# MCU_oscilliation.net
KiCad netlist of a schematic drawn in Altium Designer
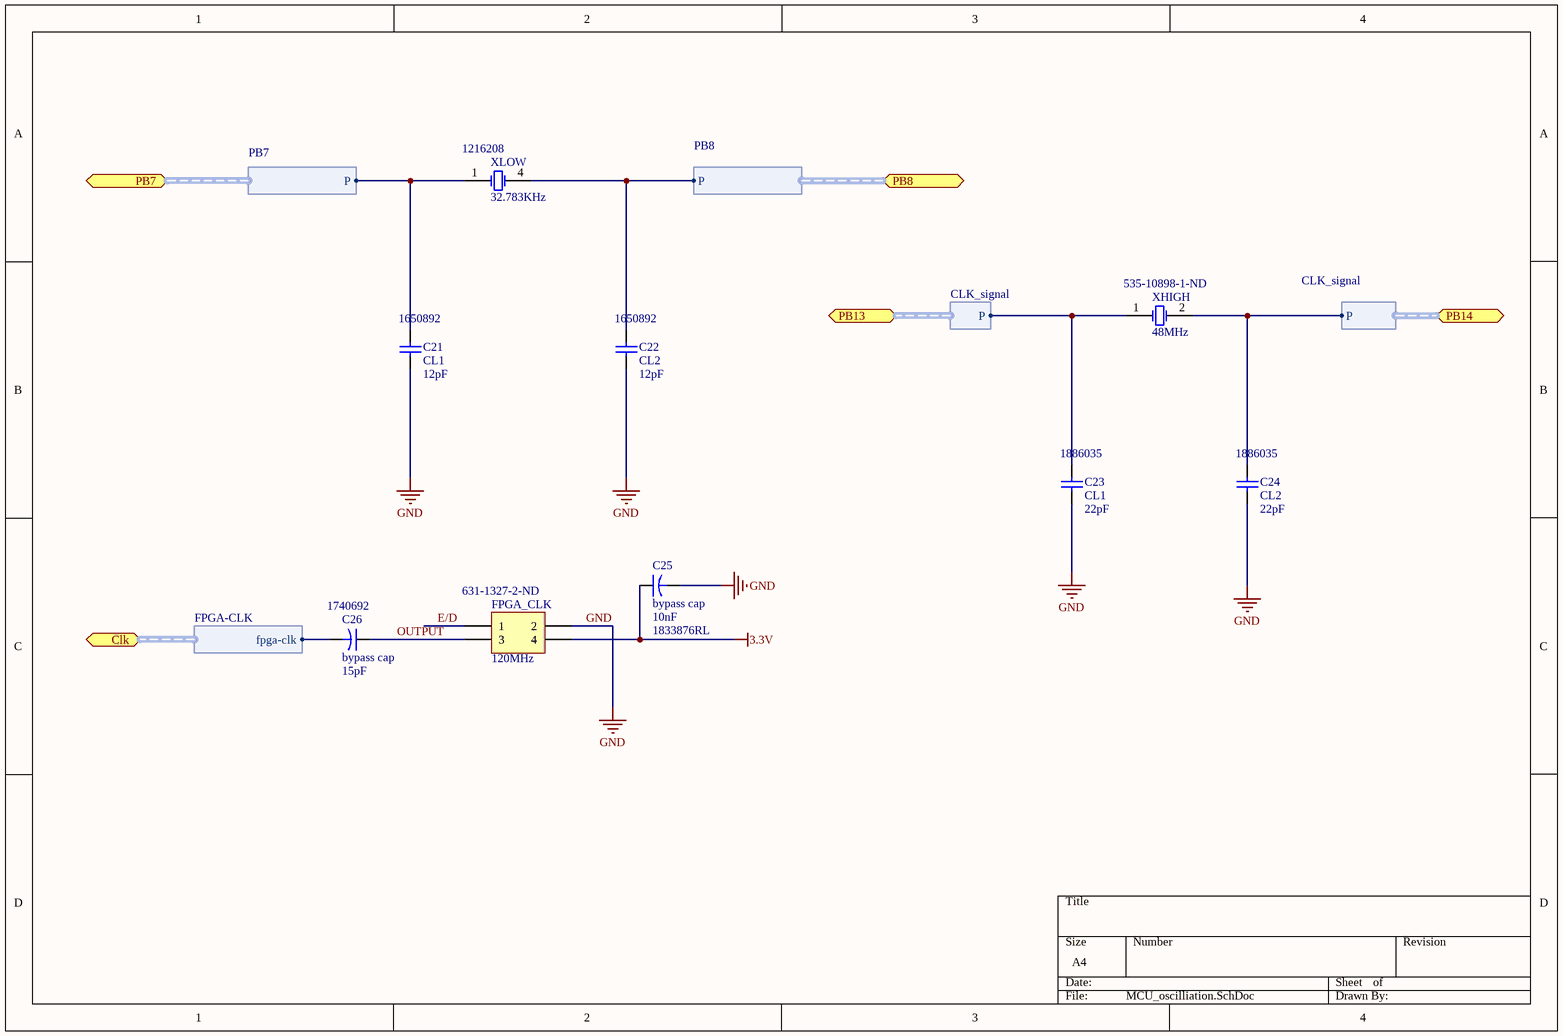
[diagram p0: MCU_oscilliation.SchDoc]

(export (version "E")
  (design (tool "Eeschema 10.0.6"))
  (components
    (comp (ref "C21")
      (value "CL1")
      (footprint "C1206")
      (description "Capacitor (Semiconductor SIM Model)")
      (fields
        (field (name "ALTIUM_VALUE") "12pF")
        (field (name "SUPPLIER PART NUMBER 1") "1650892")
        (field (name "MANUFACTURER") "KEMET")
        (field (name "MANUFACTURER PART NUMBER") "C1206C120J5GACTU")
        (field (name "PUBLISHER") "Altium Limited")
      )
      (libsource (lib "Miscellaneous Devices") (part "Cap Semi"))
    )
    (comp (ref "C22")
      (value "CL2")
      (footprint "C1206")
      (description "Capacitor (Semiconductor SIM Model)")
      (fields
        (field (name "ALTIUM_VALUE") "12pF")
        (field (name "SUPPLIER PART NUMBER 1") "1650892")
        (field (name "MANUFACTURER") "KEMET")
        (field (name "MANUFACTURER PART NUMBER") "C1206C120J5GACTU")
        (field (name "PUBLISHER") "Altium Limited")
      )
      (libsource (lib "Miscellaneous Devices") (part "Cap Semi"))
    )
    (comp (ref "C23")
      (value "CL1")
      (footprint "C1206")
      (description "Capacitor (Semiconductor SIM Model)")
      (fields
        (field (name "ALTIUM_VALUE") "22pF")
        (field (name "SUPPLIER PART NUMBER 1") "1886035")
        (field (name "MANUFACTURER") "JOHANSON DIELECTRICS")
        (field (name "MANUFACTURER PART NUMBER") "102R18N220JV4E")
        (field (name "PUBLISHER") "Altium Limited")
      )
      (libsource (lib "Miscellaneous Devices") (part "Cap Semi"))
    )
    (comp (ref "C24")
      (value "CL2")
      (footprint "C1206")
      (description "Capacitor (Semiconductor SIM Model)")
      (fields
        (field (name "ALTIUM_VALUE") "22pF")
        (field (name "SUPPLIER PART NUMBER 1") "1886035")
        (field (name "MANUFACTURER") "JOHANSON DIELECTRICS")
        (field (name "MANUFACTURER PART NUMBER") "102R18N220JV4E")
        (field (name "PUBLISHER") "Altium Limited")
      )
      (libsource (lib "Miscellaneous Devices") (part "Cap Semi"))
    )
    (comp (ref "C25")
      (value "bypass cap")
      (footprint "C1206")
      (description "Capacitor")
      (fields
        (field (name "ALTIUM_VALUE") "10nF")
        (field (name "MANUFACTURER") "AVX")
        (field (name "MANUFACTURER PART NUMBER") "06031C103JAT2A")
        (field (name "SUPPLIER PART NUMBER 1") "1833876RL")
        (field (name "PUBLISHER") "Altium Limited")
      )
      (libsource (lib "Miscellaneous Devices") (part "Cap2"))
    )
    (comp (ref "C26")
      (value "bypass cap")
      (footprint "C1206")
      (description "Capacitor")
      (fields
        (field (name "ALTIUM_VALUE") "15pF")
        (field (name "MANUFACTURER") "AVX")
        (field (name "MANUFACTURER PART NUMBER") "06031C103JAT2A")
        (field (name "SUPPLIER PART NUMBER 1") "1740692")
        (field (name "PUBLISHER") "Altium Limited")
      )
      (libsource (lib "Miscellaneous Devices") (part "Cap2"))
    )
    (comp (ref "FPGA_CLK")
      (value "120MHz")
      (footprint "OSCI-4FPGA")
      (description "Header, 2-Pin, Dual row")
      (fields
        (field (name "SUPPLIER PART NUMBER 1") "631-1327-2-ND")
        (field (name "MANUFACTURER") "Fox Electronics")
        (field (name "MANUFACTURER PART NUMBER") "FXO-HC736R-120")
        (field (name "PUBLISHER") "Altium Limited")
      )
      (libsource (lib "Miscellaneous Connectors") (part "Header 2X2"))
    )
    (comp (ref "XHIGH")
      (value "48MHz")
      (footprint "XTAL-85")
      (description "Crystal Oscillator")
      (fields
        (field (name "SUPPLIER PART NUMBER 1") "535-10898-1-ND")
        (field (name "MANUFACTURER") "Abracon Corporation")
        (field (name "MANUFACTURER PART NUMBER") "ABM2-48.000MHZ-D4YF-T")
        (field (name "PUBLISHER") "Altium Limited")
      )
      (libsource (lib "Miscellaneous Devices") (part "XTAL"))
    )
    (comp (ref "XLOW")
      (value "32.783KHz")
      (description "Crystal Oscillator")
      (fields
        (field (name "SUPPLIER PART NUMBER 1") "1216208")
        (field (name "MANUFACTURER") "EPSON")
        (field (name "MANUFACTURER PART NUMBER") "Q13MC30610003")
        (field (name "PUBLISHER") "Altium Limited")
      )
      (libsource (lib "") (part "XTAL_1"))
    )
  )
  (nets
    (net (code "5") (name "/E{slash}D") (class "Default")
      (node (ref "FPGA_CLK") (pin "1") (pinfunction "1_1") (pintype "passive"))
    )
    (net (code "6") (name "/OUTPUT") (class "Default")
      (node (ref "C26") (pin "1") (pinfunction "1_1") (pintype "passive"))
      (node (ref "FPGA_CLK") (pin "3") (pinfunction "3_3") (pintype "passive"))
    )
    (net (code "7") (name "/fpga-clk") (class "Default")
      (node (ref "C26") (pin "2") (pinfunction "2_2") (pintype "passive"))
    )
    (net (code "12") (name "3.3V") (class "Default")
      (node (ref "C25") (pin "1") (pinfunction "1_1") (pintype "passive"))
      (node (ref "FPGA_CLK") (pin "4") (pinfunction "4_4") (pintype "passive"))
    )
    (net (code "13") (name "GND") (class "Default")
      (node (ref "C21") (pin "1") (pinfunction "1_1") (pintype "passive"))
      (node (ref "C22") (pin "1") (pinfunction "1_1") (pintype "passive"))
      (node (ref "C23") (pin "1") (pinfunction "1_1") (pintype "passive"))
      (node (ref "C24") (pin "1") (pinfunction "1_1") (pintype "passive"))
      (node (ref "C25") (pin "2") (pinfunction "2_2") (pintype "passive"))
      (node (ref "FPGA_CLK") (pin "2") (pinfunction "2_2") (pintype "passive"))
    )
    (net (code "14") (name "Net-(XHIGH-OSC1)") (class "Default")
      (node (ref "C23") (pin "2") (pinfunction "2_2") (pintype "passive"))
      (node (ref "XHIGH") (pin "1") (pinfunction "OSC1_1") (pintype "passive"))
    )
    (net (code "15") (name "Net-(XHIGH-OSC2)") (class "Default")
      (node (ref "C24") (pin "2") (pinfunction "2_2") (pintype "passive"))
      (node (ref "XHIGH") (pin "2") (pinfunction "OSC2_2") (pintype "passive"))
    )
    (net (code "16") (name "Net-(XLOW-OSC1)") (class "Default")
      (node (ref "C21") (pin "2") (pinfunction "2_2") (pintype "passive"))
      (node (ref "XLOW") (pin "1") (pinfunction "OSC1_1") (pintype "passive"))
    )
    (net (code "17") (name "Net-(XLOW-OSC2)") (class "Default")
      (node (ref "C22") (pin "2") (pinfunction "2_2") (pintype "passive"))
      (node (ref "XLOW") (pin "4") (pinfunction "OSC2_4") (pintype "passive"))
    )
  )
)
